# BigMuff.net
KiCad netlist of a schematic drawn in EAGLE
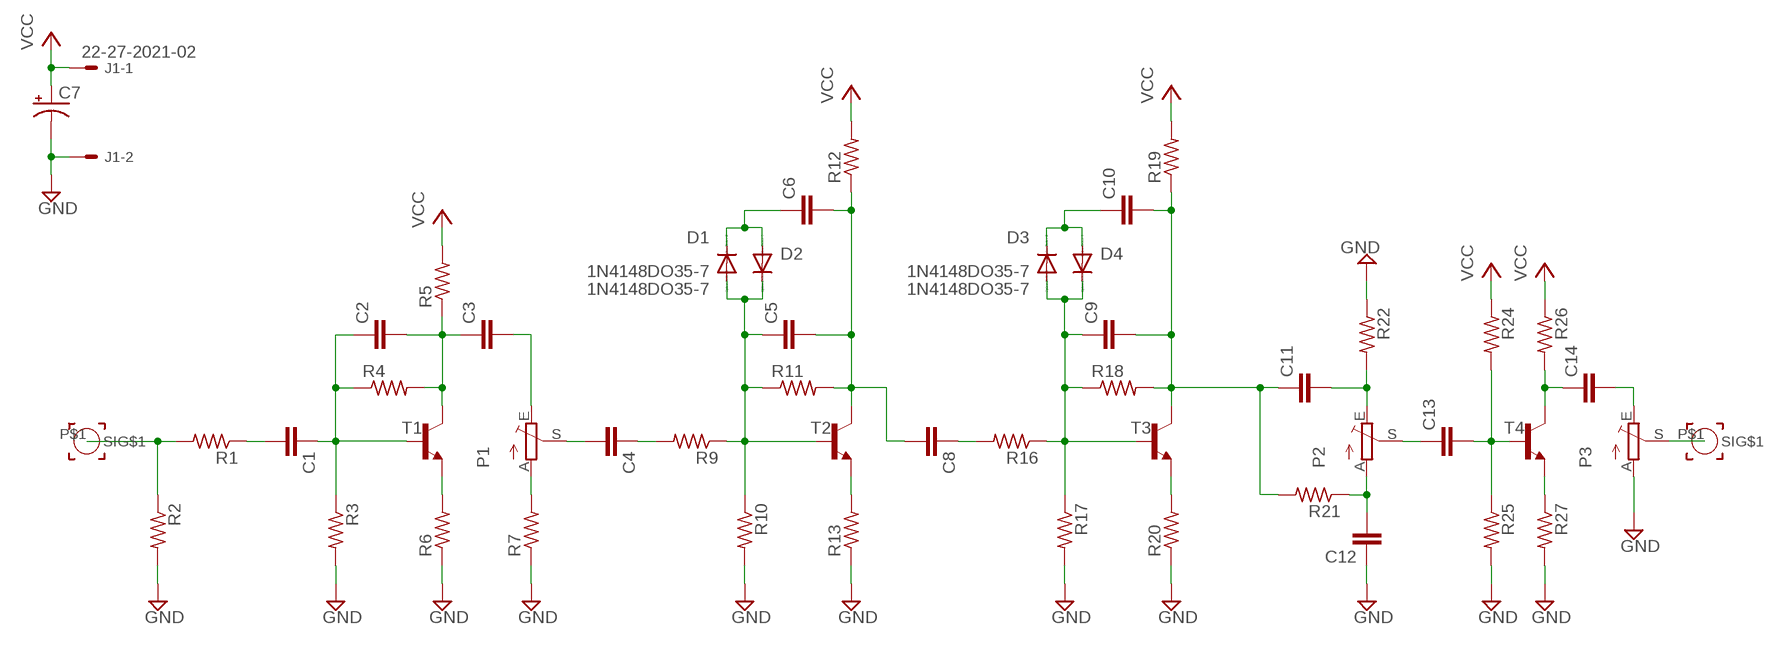
[diagram p0: schematic, sheet 1]

(export (version "E")
  (design (tool "Eeschema 10.0.6"))
  (components
    (comp (ref "C1")
      (value "C-EU050-024X044-BP")
      (footprint "eagle-import:C050-024X044-BP")
      (libsource (lib "eagle-import") (part "C-EU050-024X044-BP"))
    )
    (comp (ref "C2")
      (value "C-EU050-024X044-BP")
      (footprint "eagle-import:C050-024X044-BP")
      (libsource (lib "eagle-import") (part "C-EU050-024X044-BP"))
    )
    (comp (ref "C3")
      (value "C-EU050-024X044-BP")
      (footprint "eagle-import:C050-024X044-BP")
      (libsource (lib "eagle-import") (part "C-EU050-024X044-BP"))
    )
    (comp (ref "C4")
      (value "C-EU050-024X044-BP")
      (footprint "eagle-import:C050-024X044-BP")
      (libsource (lib "eagle-import") (part "C-EU050-024X044-BP"))
    )
    (comp (ref "C5")
      (value "C-EU050-024X044-BP")
      (footprint "eagle-import:C050-024X044-BP")
      (libsource (lib "eagle-import") (part "C-EU050-024X044-BP"))
    )
    (comp (ref "C6")
      (value "C-EU050-024X044-BP")
      (footprint "eagle-import:C050-024X044-BP")
      (libsource (lib "eagle-import") (part "C-EU050-024X044-BP"))
    )
    (comp (ref "C7")
      (value "CPOL-USE2.5-7")
      (footprint "eagle-import:E2,5-7")
      (libsource (lib "eagle-import") (part "CPOL-USE2.5-7"))
    )
    (comp (ref "C8")
      (value "C-EU050-024X044-BP")
      (footprint "eagle-import:C050-024X044-BP")
      (libsource (lib "eagle-import") (part "C-EU050-024X044-BP"))
    )
    (comp (ref "C9")
      (value "C-EU050-024X044-BP")
      (footprint "eagle-import:C050-024X044-BP")
      (libsource (lib "eagle-import") (part "C-EU050-024X044-BP"))
    )
    (comp (ref "C10")
      (value "C-EU050-024X044-BP")
      (footprint "eagle-import:C050-024X044-BP")
      (libsource (lib "eagle-import") (part "C-EU050-024X044-BP"))
    )
    (comp (ref "C11")
      (value "C-EU050-024X044-BP")
      (footprint "eagle-import:C050-024X044-BP")
      (libsource (lib "eagle-import") (part "C-EU050-024X044-BP"))
    )
    (comp (ref "C12")
      (value "C-EU050-024X044-BP")
      (footprint "eagle-import:C050-024X044-BP")
      (libsource (lib "eagle-import") (part "C-EU050-024X044-BP"))
    )
    (comp (ref "C13")
      (value "C-EU050-024X044-BP")
      (footprint "eagle-import:C050-024X044-BP")
      (libsource (lib "eagle-import") (part "C-EU050-024X044-BP"))
    )
    (comp (ref "C14")
      (value "C-EU050-024X044-BP")
      (footprint "eagle-import:C050-024X044-BP")
      (libsource (lib "eagle-import") (part "C-EU050-024X044-BP"))
    )
    (comp (ref "D1")
      (value "1N4148DO35-7")
      (footprint "eagle-import:DO35-7")
      (libsource (lib "eagle-import") (part "1N4148DO35-7"))
    )
    (comp (ref "D2")
      (value "1N4148DO35-7")
      (footprint "eagle-import:DO35-7")
      (libsource (lib "eagle-import") (part "1N4148DO35-7"))
    )
    (comp (ref "D3")
      (value "1N4148DO35-7")
      (footprint "eagle-import:DO35-7")
      (libsource (lib "eagle-import") (part "1N4148DO35-7"))
    )
    (comp (ref "D4")
      (value "1N4148DO35-7")
      (footprint "eagle-import:DO35-7")
      (libsource (lib "eagle-import") (part "1N4148DO35-7"))
    )
    (comp (ref "J1")
      (value "22-27-2021-02")
      (footprint "eagle-import:6410-02")
      (libsource (lib "eagle-import") (part "22-?-0227-2021"))
    )
    (comp (ref "P1")
      (value "TRIM_EU-S64W")
      (footprint "eagle-import:S64W")
      (libsource (lib "eagle-import") (part "TRIM_EU-S64W"))
    )
    (comp (ref "P2")
      (value "TRIM_EU-S64W")
      (footprint "eagle-import:S64W")
      (libsource (lib "eagle-import") (part "TRIM_EU-S64W"))
    )
    (comp (ref "P3")
      (value "TRIM_EU-S64W")
      (footprint "eagle-import:S64W")
      (libsource (lib "eagle-import") (part "TRIM_EU-S64W"))
    )
    (comp (ref "R1")
      (value "R-US_0204/5-BP")
      (footprint "eagle-import:0204_5-BP")
      (libsource (lib "eagle-import") (part "R-US_0204/5-BP"))
    )
    (comp (ref "R2")
      (value "R-US_0204/5-BP")
      (footprint "eagle-import:0204_5-BP")
      (libsource (lib "eagle-import") (part "R-US_0204/5-BP"))
    )
    (comp (ref "R3")
      (value "R-US_0204/5-BP")
      (footprint "eagle-import:0204_5-BP")
      (libsource (lib "eagle-import") (part "R-US_0204/5-BP"))
    )
    (comp (ref "R4")
      (value "R-US_0204/5-BP")
      (footprint "eagle-import:0204_5-BP")
      (libsource (lib "eagle-import") (part "R-US_0204/5-BP"))
    )
    (comp (ref "R5")
      (value "R-US_0204/5-BP")
      (footprint "eagle-import:0204_5-BP")
      (libsource (lib "eagle-import") (part "R-US_0204/5-BP"))
    )
    (comp (ref "R6")
      (value "R-US_0204/5-BP")
      (footprint "eagle-import:0204_5-BP")
      (libsource (lib "eagle-import") (part "R-US_0204/5-BP"))
    )
    (comp (ref "R7")
      (value "R-US_0204/5-BP")
      (footprint "eagle-import:0204_5-BP")
      (libsource (lib "eagle-import") (part "R-US_0204/5-BP"))
    )
    (comp (ref "R9")
      (value "R-US_0204/5-BP")
      (footprint "eagle-import:0204_5-BP")
      (libsource (lib "eagle-import") (part "R-US_0204/5-BP"))
    )
    (comp (ref "R10")
      (value "R-US_0204/5-BP")
      (footprint "eagle-import:0204_5-BP")
      (libsource (lib "eagle-import") (part "R-US_0204/5-BP"))
    )
    (comp (ref "R11")
      (value "R-US_0204/5-BP")
      (footprint "eagle-import:0204_5-BP")
      (libsource (lib "eagle-import") (part "R-US_0204/5-BP"))
    )
    (comp (ref "R12")
      (value "R-US_0204/5-BP")
      (footprint "eagle-import:0204_5-BP")
      (libsource (lib "eagle-import") (part "R-US_0204/5-BP"))
    )
    (comp (ref "R13")
      (value "R-US_0204/5-BP")
      (footprint "eagle-import:0204_5-BP")
      (libsource (lib "eagle-import") (part "R-US_0204/5-BP"))
    )
    (comp (ref "R16")
      (value "R-US_0204/5-BP")
      (footprint "eagle-import:0204_5-BP")
      (libsource (lib "eagle-import") (part "R-US_0204/5-BP"))
    )
    (comp (ref "R17")
      (value "R-US_0204/5-BP")
      (footprint "eagle-import:0204_5-BP")
      (libsource (lib "eagle-import") (part "R-US_0204/5-BP"))
    )
    (comp (ref "R18")
      (value "R-US_0204/5-BP")
      (footprint "eagle-import:0204_5-BP")
      (libsource (lib "eagle-import") (part "R-US_0204/5-BP"))
    )
    (comp (ref "R19")
      (value "R-US_0204/5-BP")
      (footprint "eagle-import:0204_5-BP")
      (libsource (lib "eagle-import") (part "R-US_0204/5-BP"))
    )
    (comp (ref "R20")
      (value "R-US_0204/5-BP")
      (footprint "eagle-import:0204_5-BP")
      (libsource (lib "eagle-import") (part "R-US_0204/5-BP"))
    )
    (comp (ref "R21")
      (value "R-US_0204/5-BP")
      (footprint "eagle-import:0204_5-BP")
      (libsource (lib "eagle-import") (part "R-US_0204/5-BP"))
    )
    (comp (ref "R22")
      (value "R-US_0204/5-BP")
      (footprint "eagle-import:0204_5-BP")
      (libsource (lib "eagle-import") (part "R-US_0204/5-BP"))
    )
    (comp (ref "R24")
      (value "R-US_0204/5-BP")
      (footprint "eagle-import:0204_5-BP")
      (libsource (lib "eagle-import") (part "R-US_0204/5-BP"))
    )
    (comp (ref "R25")
      (value "R-US_0204/5-BP")
      (footprint "eagle-import:0204_5-BP")
      (libsource (lib "eagle-import") (part "R-US_0204/5-BP"))
    )
    (comp (ref "R26")
      (value "R-US_0204/5-BP")
      (footprint "eagle-import:0204_5-BP")
      (libsource (lib "eagle-import") (part "R-US_0204/5-BP"))
    )
    (comp (ref "R27")
      (value "R-US_0204/5-BP")
      (footprint "eagle-import:0204_5-BP")
      (libsource (lib "eagle-import") (part "R-US_0204/5-BP"))
    )
    (comp (ref "T1")
      (value "-NPN-TO92-EBC")
      (footprint "eagle-import:TO92-EBC")
      (libsource (lib "eagle-import") (part "-NPN-TO92-EBC"))
    )
    (comp (ref "T2")
      (value "-NPN-TO92-EBC")
      (footprint "eagle-import:TO92-EBC")
      (libsource (lib "eagle-import") (part "-NPN-TO92-EBC"))
    )
    (comp (ref "T3")
      (value "-NPN-TO92-EBC")
      (footprint "eagle-import:TO92-EBC")
      (libsource (lib "eagle-import") (part "-NPN-TO92-EBC"))
    )
    (comp (ref "T4")
      (value "-NPN-TO92-EBC")
      (footprint "eagle-import:TO92-EBC")
      (libsource (lib "eagle-import") (part "-NPN-TO92-EBC"))
    )
    (comp (ref "U$1")
      (value "SIGNAL_PAD")
      (footprint "eagle-import:SIGNAL_PAD")
      (libsource (lib "eagle-import") (part "SIGNAL_PAD"))
    )
    (comp (ref "U$2")
      (value "SIGNAL_PAD")
      (footprint "eagle-import:SIGNAL_PAD")
      (libsource (lib "eagle-import") (part "SIGNAL_PAD"))
    )
  )
  (nets
    (net (code "1") (name "GND") (class "Default")
      (node (ref "C12") (pin "1") (pinfunction "1_1") (pintype "passive"))
      (node (ref "C7") (pin "-") (pinfunction "-_-") (pintype "passive"))
      (node (ref "J1") (pin "2") (pinfunction "S_2") (pintype "passive"))
      (node (ref "P3") (pin "A") (pinfunction "A_A") (pintype "passive"))
      (node (ref "R10") (pin "2") (pinfunction "2_2") (pintype "passive"))
      (node (ref "R13") (pin "1") (pinfunction "1_1") (pintype "passive"))
      (node (ref "R17") (pin "2") (pinfunction "2_2") (pintype "passive"))
      (node (ref "R2") (pin "2") (pinfunction "2_2") (pintype "passive"))
      (node (ref "R20") (pin "1") (pinfunction "1_1") (pintype "passive"))
      (node (ref "R22") (pin "1") (pinfunction "1_1") (pintype "passive"))
      (node (ref "R25") (pin "2") (pinfunction "2_2") (pintype "passive"))
      (node (ref "R27") (pin "2") (pinfunction "2_2") (pintype "passive"))
      (node (ref "R3") (pin "2") (pinfunction "2_2") (pintype "passive"))
      (node (ref "R6") (pin "1") (pinfunction "1_1") (pintype "passive"))
      (node (ref "R7") (pin "1") (pinfunction "1_1") (pintype "passive"))
    )
    (net (code "2") (name "Net-(C1-Pad1)") (class "Default")
      (node (ref "C1") (pin "1") (pinfunction "1_1") (pintype "passive"))
      (node (ref "C2") (pin "1") (pinfunction "1_1") (pintype "passive"))
      (node (ref "R3") (pin "1") (pinfunction "1_1") (pintype "passive"))
      (node (ref "R4") (pin "1") (pinfunction "1_1") (pintype "passive"))
      (node (ref "T1") (pin "B") (pinfunction "B_B") (pintype "passive"))
    )
    (net (code "3") (name "Net-(C1-Pad2)") (class "Default")
      (node (ref "C1") (pin "2") (pinfunction "2_2") (pintype "passive"))
      (node (ref "R1") (pin "1") (pinfunction "1_1") (pintype "passive"))
    )
    (net (code "4") (name "Net-(C2-Pad2)") (class "Default")
      (node (ref "C2") (pin "2") (pinfunction "2_2") (pintype "passive"))
      (node (ref "C3") (pin "1") (pinfunction "1_1") (pintype "passive"))
      (node (ref "R4") (pin "2") (pinfunction "2_2") (pintype "passive"))
      (node (ref "R5") (pin "1") (pinfunction "1_1") (pintype "passive"))
      (node (ref "T1") (pin "C") (pinfunction "C_C") (pintype "passive"))
    )
    (net (code "5") (name "Net-(C3-Pad2)") (class "Default")
      (node (ref "C3") (pin "2") (pinfunction "2_2") (pintype "passive"))
      (node (ref "P1") (pin "E") (pinfunction "E_E") (pintype "passive"))
    )
    (net (code "6") (name "Net-(C4-Pad1)") (class "Default")
      (node (ref "C4") (pin "1") (pinfunction "1_1") (pintype "passive"))
      (node (ref "R9") (pin "2") (pinfunction "2_2") (pintype "passive"))
    )
    (net (code "7") (name "Net-(C4-Pad2)") (class "Default")
      (node (ref "C4") (pin "2") (pinfunction "2_2") (pintype "passive"))
      (node (ref "P1") (pin "S") (pinfunction "S_S") (pintype "passive"))
    )
    (net (code "8") (name "Net-(C5-Pad1)") (class "Default")
      (node (ref "C5") (pin "1") (pinfunction "1_1") (pintype "passive"))
      (node (ref "D1") (pin "A") (pinfunction "A_A") (pintype "passive"))
      (node (ref "D2") (pin "C") (pinfunction "C_C") (pintype "passive"))
      (node (ref "R10") (pin "1") (pinfunction "1_1") (pintype "passive"))
      (node (ref "R11") (pin "1") (pinfunction "1_1") (pintype "passive"))
      (node (ref "R9") (pin "1") (pinfunction "1_1") (pintype "passive"))
      (node (ref "T2") (pin "B") (pinfunction "B_B") (pintype "passive"))
    )
    (net (code "9") (name "Net-(C5-Pad2)") (class "Default")
      (node (ref "C5") (pin "2") (pinfunction "2_2") (pintype "passive"))
      (node (ref "C6") (pin "2") (pinfunction "2_2") (pintype "passive"))
      (node (ref "C8") (pin "2") (pinfunction "2_2") (pintype "passive"))
      (node (ref "R11") (pin "2") (pinfunction "2_2") (pintype "passive"))
      (node (ref "R12") (pin "1") (pinfunction "1_1") (pintype "passive"))
      (node (ref "T2") (pin "C") (pinfunction "C_C") (pintype "passive"))
    )
    (net (code "10") (name "Net-(C6-Pad1)") (class "Default")
      (node (ref "C6") (pin "1") (pinfunction "1_1") (pintype "passive"))
      (node (ref "D1") (pin "C") (pinfunction "C_C") (pintype "passive"))
      (node (ref "D2") (pin "A") (pinfunction "A_A") (pintype "passive"))
    )
    (net (code "11") (name "Net-(C8-Pad1)") (class "Default")
      (node (ref "C8") (pin "1") (pinfunction "1_1") (pintype "passive"))
      (node (ref "R16") (pin "2") (pinfunction "2_2") (pintype "passive"))
    )
    (net (code "12") (name "Net-(C9-Pad1)") (class "Default")
      (node (ref "C9") (pin "1") (pinfunction "1_1") (pintype "passive"))
      (node (ref "D3") (pin "A") (pinfunction "A_A") (pintype "passive"))
      (node (ref "D4") (pin "C") (pinfunction "C_C") (pintype "passive"))
      (node (ref "R16") (pin "1") (pinfunction "1_1") (pintype "passive"))
      (node (ref "R17") (pin "1") (pinfunction "1_1") (pintype "passive"))
      (node (ref "R18") (pin "1") (pinfunction "1_1") (pintype "passive"))
      (node (ref "T3") (pin "B") (pinfunction "B_B") (pintype "passive"))
    )
    (net (code "13") (name "Net-(C10-Pad1)") (class "Default")
      (node (ref "C10") (pin "1") (pinfunction "1_1") (pintype "passive"))
      (node (ref "D3") (pin "C") (pinfunction "C_C") (pintype "passive"))
      (node (ref "D4") (pin "A") (pinfunction "A_A") (pintype "passive"))
    )
    (net (code "14") (name "Net-(C10-Pad2)") (class "Default")
      (node (ref "C10") (pin "2") (pinfunction "2_2") (pintype "passive"))
      (node (ref "C11") (pin "1") (pinfunction "1_1") (pintype "passive"))
      (node (ref "C9") (pin "2") (pinfunction "2_2") (pintype "passive"))
      (node (ref "R18") (pin "2") (pinfunction "2_2") (pintype "passive"))
      (node (ref "R19") (pin "1") (pinfunction "1_1") (pintype "passive"))
      (node (ref "R21") (pin "2") (pinfunction "2_2") (pintype "passive"))
      (node (ref "T3") (pin "C") (pinfunction "C_C") (pintype "passive"))
    )
    (net (code "15") (name "Net-(C11-Pad2)") (class "Default")
      (node (ref "C11") (pin "2") (pinfunction "2_2") (pintype "passive"))
      (node (ref "P2") (pin "E") (pinfunction "E_E") (pintype "passive"))
      (node (ref "R22") (pin "2") (pinfunction "2_2") (pintype "passive"))
    )
    (net (code "16") (name "Net-(C12-Pad2)") (class "Default")
      (node (ref "C12") (pin "2") (pinfunction "2_2") (pintype "passive"))
      (node (ref "P2") (pin "A") (pinfunction "A_A") (pintype "passive"))
      (node (ref "R21") (pin "1") (pinfunction "1_1") (pintype "passive"))
    )
    (net (code "17") (name "Net-(C13-Pad1)") (class "Default")
      (node (ref "C13") (pin "1") (pinfunction "1_1") (pintype "passive"))
      (node (ref "P2") (pin "S") (pinfunction "S_S") (pintype "passive"))
    )
    (net (code "18") (name "Net-(C13-Pad2)") (class "Default")
      (node (ref "C13") (pin "2") (pinfunction "2_2") (pintype "passive"))
      (node (ref "R24") (pin "2") (pinfunction "2_2") (pintype "passive"))
      (node (ref "R25") (pin "1") (pinfunction "1_1") (pintype "passive"))
      (node (ref "T4") (pin "B") (pinfunction "B_B") (pintype "passive"))
    )
    (net (code "19") (name "Net-(C14-Pad1)") (class "Default")
      (node (ref "C14") (pin "1") (pinfunction "1_1") (pintype "passive"))
      (node (ref "R26") (pin "2") (pinfunction "2_2") (pintype "passive"))
      (node (ref "T4") (pin "C") (pinfunction "C_C") (pintype "passive"))
    )
    (net (code "20") (name "Net-(C14-Pad2)") (class "Default")
      (node (ref "C14") (pin "2") (pinfunction "2_2") (pintype "passive"))
      (node (ref "P3") (pin "E") (pinfunction "E_E") (pintype "passive"))
    )
    (net (code "21") (name "Net-(P1-PadA)") (class "Default")
      (node (ref "P1") (pin "A") (pinfunction "A_A") (pintype "passive"))
      (node (ref "R7") (pin "2") (pinfunction "2_2") (pintype "passive"))
    )
    (net (code "22") (name "Net-(R6-Pad2)") (class "Default")
      (node (ref "R6") (pin "2") (pinfunction "2_2") (pintype "passive"))
      (node (ref "T1") (pin "E") (pinfunction "E_E") (pintype "passive"))
    )
    (net (code "23") (name "Net-(R13-Pad2)") (class "Default")
      (node (ref "R13") (pin "2") (pinfunction "2_2") (pintype "passive"))
      (node (ref "T2") (pin "E") (pinfunction "E_E") (pintype "passive"))
    )
    (net (code "24") (name "Net-(R20-Pad2)") (class "Default")
      (node (ref "R20") (pin "2") (pinfunction "2_2") (pintype "passive"))
      (node (ref "T3") (pin "E") (pinfunction "E_E") (pintype "passive"))
    )
    (net (code "25") (name "Net-(R27-Pad1)") (class "Default")
      (node (ref "R27") (pin "1") (pinfunction "1_1") (pintype "passive"))
      (node (ref "T4") (pin "E") (pinfunction "E_E") (pintype "passive"))
    )
    (net (code "26") (name "Net-(U$1-SIG$1)") (class "Default")
      (node (ref "R1") (pin "2") (pinfunction "2_2") (pintype "passive"))
      (node (ref "R2") (pin "1") (pinfunction "1_1") (pintype "passive"))
      (node (ref "U$1") (pin "P$1") (pinfunction "SIG$1_P$1") (pintype "bidirectional"))
    )
    (net (code "27") (name "Net-(U$2-SIG$1)") (class "Default")
      (node (ref "P3") (pin "S") (pinfunction "S_S") (pintype "passive"))
      (node (ref "U$2") (pin "P$1") (pinfunction "SIG$1_P$1") (pintype "bidirectional"))
    )
    (net (code "28") (name "VCC") (class "Default")
      (node (ref "C7") (pin "+") (pinfunction "+_+") (pintype "passive"))
      (node (ref "J1") (pin "1") (pinfunction "S_1") (pintype "passive"))
      (node (ref "R12") (pin "2") (pinfunction "2_2") (pintype "passive"))
      (node (ref "R19") (pin "2") (pinfunction "2_2") (pintype "passive"))
      (node (ref "R24") (pin "1") (pinfunction "1_1") (pintype "passive"))
      (node (ref "R26") (pin "1") (pinfunction "1_1") (pintype "passive"))
      (node (ref "R5") (pin "2") (pinfunction "2_2") (pintype "passive"))
    )
  )
)
